# SCH_SecureGuardianDevice_2024-06-15.net
KiCad netlist of a schematic drawn in EasyEDA
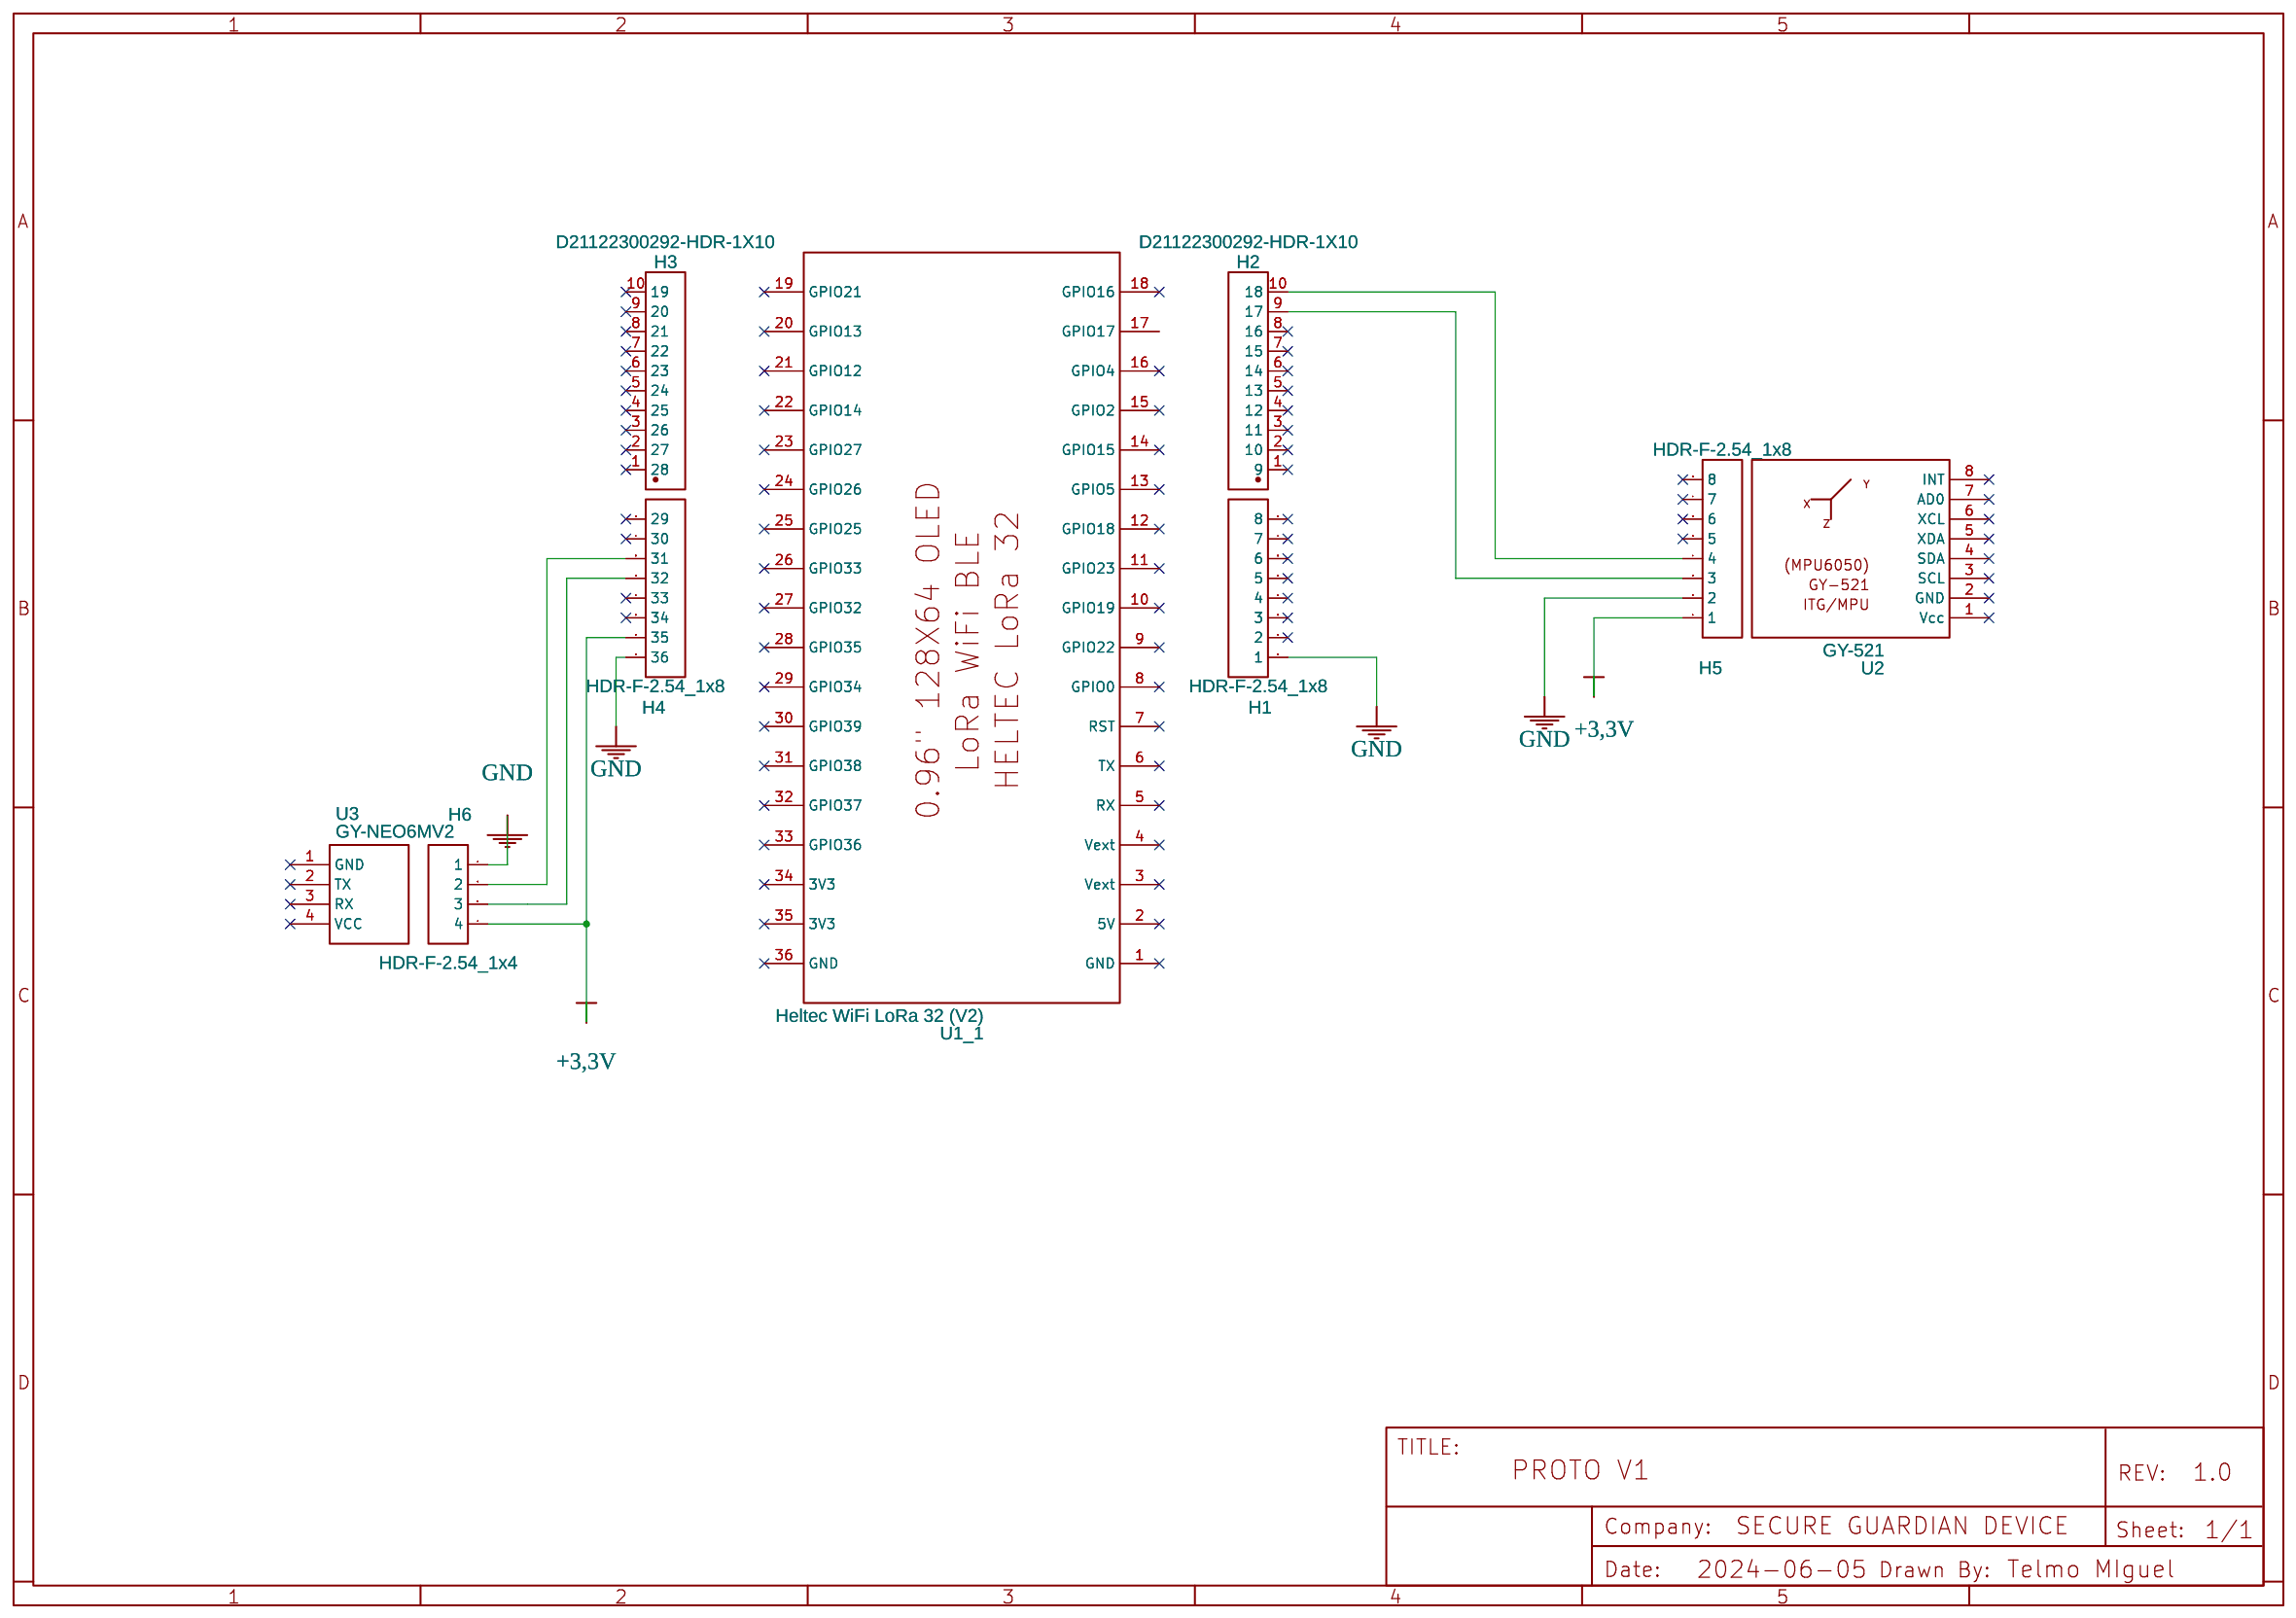
[diagram p0: schematic sheet]

(export (version "E")
  (design (tool "Eeschema 10.0.6"))
  (components
    (comp (ref "H1") (value "HDR-F-2.54_1x8") (libsource (lib "") (part "HDR-F-2.54_1x8")))
    (comp (ref "H2") (value "D21122300292-HDR-1X10") (libsource (lib "") (part "D21122300292-HDR-1X10")))
    (comp (ref "H3") (value "D21122300292-HDR-1X10") (libsource (lib "") (part "D21122300292-HDR-1X10_1")))
    (comp (ref "H4") (value "HDR-F-2.54_1x8") (libsource (lib "") (part "HDR-F-2.54_1x8_1")))
    (comp (ref "H5") (value "HDR-F-2.54_1x8") (libsource (lib "") (part "HDR-F-2.54_1x8_2")))
    (comp (ref "H6") (value "HDR-F-2.54_1x4") (libsource (lib "") (part "HDR-F-2.54_1x4")))
    (comp (ref "U1_1")
      (value "Heltec WiFi LoRa 32 (V2)")
      (fields
        (field (name "Manufacturer Part") "Heltec WiFi LoRa 32(V2)")
        (field (name "Manufacturer") "Heltec")
      )
      (libsource (lib "") (part "Heltec WiFi LoRa 32 (V2)"))
    )
    (comp (ref "U2") (value "GY-521") (libsource (lib "") (part "GY-521")))
    (comp (ref "U3") (value "GY-NEO6MV2") (libsource (lib "") (part "GY-NEO6MV2")))
  )
  (nets
    (net (code "1") (name "+3,3V") (class "Default")
      (node (ref "H4") (pin "2") (pinfunction "35_2") (pintype "unspecified"))
      (node (ref "H5") (pin "1") (pinfunction "1_1") (pintype "unspecified"))
      (node (ref "H6") (pin "4") (pinfunction "4_4") (pintype "unspecified"))
    )
    (net (code "2") (name "GND") (class "Default")
      (node (ref "H1") (pin "1") (pinfunction "1_1") (pintype "unspecified"))
      (node (ref "H4") (pin "1") (pinfunction "36_1") (pintype "unspecified"))
      (node (ref "H5") (pin "2") (pinfunction "2_2") (pintype "unspecified"))
      (node (ref "H6") (pin "1") (pinfunction "1_1") (pintype "unspecified"))
    )
    (net (code "3") (name "Net-(H2-17)") (class "Default")
      (node (ref "H2") (pin "9") (pinfunction "17_9") (pintype "unspecified"))
      (node (ref "H5") (pin "3") (pinfunction "3_3") (pintype "unspecified"))
    )
    (net (code "4") (name "Net-(H2-18)") (class "Default")
      (node (ref "H2") (pin "10") (pinfunction "18_10") (pintype "unspecified"))
      (node (ref "H5") (pin "4") (pinfunction "4_4") (pintype "unspecified"))
    )
    (net (code "5") (name "Net-(H4-31)") (class "Default")
      (node (ref "H4") (pin "6") (pinfunction "31_6") (pintype "unspecified"))
      (node (ref "H6") (pin "2") (pinfunction "2_2") (pintype "unspecified"))
    )
    (net (code "6") (name "Net-(H4-32)") (class "Default")
      (node (ref "H4") (pin "5") (pinfunction "32_5") (pintype "unspecified"))
      (node (ref "H6") (pin "3") (pinfunction "3_3") (pintype "unspecified"))
    )
    (net (code "7") (name "unconnected-(H1-Pad2)") (class "Default")
      (node (ref "H1") (pin "2") (pinfunction "2_2") (pintype "unspecified+no_connect"))
    )
    (net (code "8") (name "unconnected-(H1-Pad3)") (class "Default")
      (node (ref "H1") (pin "3") (pinfunction "3_3") (pintype "unspecified+no_connect"))
    )
    (net (code "9") (name "unconnected-(H1-Pad4)") (class "Default")
      (node (ref "H1") (pin "4") (pinfunction "4_4") (pintype "unspecified+no_connect"))
    )
    (net (code "10") (name "unconnected-(H1-Pad5)") (class "Default")
      (node (ref "H1") (pin "5") (pinfunction "5_5") (pintype "unspecified+no_connect"))
    )
    (net (code "11") (name "unconnected-(H1-Pad6)") (class "Default")
      (node (ref "H1") (pin "6") (pinfunction "6_6") (pintype "unspecified+no_connect"))
    )
    (net (code "12") (name "unconnected-(H1-Pad7)") (class "Default")
      (node (ref "H1") (pin "7") (pinfunction "7_7") (pintype "unspecified+no_connect"))
    )
    (net (code "13") (name "unconnected-(H1-Pad8)") (class "Default")
      (node (ref "H1") (pin "8") (pinfunction "8_8") (pintype "unspecified+no_connect"))
    )
    (net (code "14") (name "unconnected-(H2-9-Pad1)") (class "Default")
      (node (ref "H2") (pin "1") (pinfunction "9_1") (pintype "unspecified+no_connect"))
    )
    (net (code "15") (name "unconnected-(H2-10-Pad2)") (class "Default")
      (node (ref "H2") (pin "2") (pinfunction "10_2") (pintype "unspecified+no_connect"))
    )
    (net (code "16") (name "unconnected-(H2-11-Pad3)") (class "Default")
      (node (ref "H2") (pin "3") (pinfunction "11_3") (pintype "unspecified+no_connect"))
    )
    (net (code "17") (name "unconnected-(H2-12-Pad4)") (class "Default")
      (node (ref "H2") (pin "4") (pinfunction "12_4") (pintype "unspecified+no_connect"))
    )
    (net (code "18") (name "unconnected-(H2-13-Pad5)") (class "Default")
      (node (ref "H2") (pin "5") (pinfunction "13_5") (pintype "unspecified+no_connect"))
    )
    (net (code "19") (name "unconnected-(H2-14-Pad6)") (class "Default")
      (node (ref "H2") (pin "6") (pinfunction "14_6") (pintype "unspecified+no_connect"))
    )
    (net (code "20") (name "unconnected-(H2-15-Pad7)") (class "Default")
      (node (ref "H2") (pin "7") (pinfunction "15_7") (pintype "unspecified+no_connect"))
    )
    (net (code "21") (name "unconnected-(H2-16-Pad8)") (class "Default")
      (node (ref "H2") (pin "8") (pinfunction "16_8") (pintype "unspecified+no_connect"))
    )
    (net (code "22") (name "unconnected-(H3-19-Pad10)") (class "Default")
      (node (ref "H3") (pin "10") (pinfunction "19_10") (pintype "unspecified+no_connect"))
    )
    (net (code "23") (name "unconnected-(H3-20-Pad9)") (class "Default")
      (node (ref "H3") (pin "9") (pinfunction "20_9") (pintype "unspecified+no_connect"))
    )
    (net (code "24") (name "unconnected-(H3-21-Pad8)") (class "Default")
      (node (ref "H3") (pin "8") (pinfunction "21_8") (pintype "unspecified+no_connect"))
    )
    (net (code "25") (name "unconnected-(H3-22-Pad7)") (class "Default")
      (node (ref "H3") (pin "7") (pinfunction "22_7") (pintype "unspecified+no_connect"))
    )
    (net (code "26") (name "unconnected-(H3-23-Pad6)") (class "Default")
      (node (ref "H3") (pin "6") (pinfunction "23_6") (pintype "unspecified+no_connect"))
    )
    (net (code "27") (name "unconnected-(H3-24-Pad5)") (class "Default")
      (node (ref "H3") (pin "5") (pinfunction "24_5") (pintype "unspecified+no_connect"))
    )
    (net (code "28") (name "unconnected-(H3-25-Pad4)") (class "Default")
      (node (ref "H3") (pin "4") (pinfunction "25_4") (pintype "unspecified+no_connect"))
    )
    (net (code "29") (name "unconnected-(H3-26-Pad3)") (class "Default")
      (node (ref "H3") (pin "3") (pinfunction "26_3") (pintype "unspecified+no_connect"))
    )
    (net (code "30") (name "unconnected-(H3-27-Pad2)") (class "Default")
      (node (ref "H3") (pin "2") (pinfunction "27_2") (pintype "unspecified+no_connect"))
    )
    (net (code "31") (name "unconnected-(H3-28-Pad1)") (class "Default")
      (node (ref "H3") (pin "1") (pinfunction "28_1") (pintype "unspecified+no_connect"))
    )
    (net (code "32") (name "unconnected-(H4-29-Pad8)") (class "Default")
      (node (ref "H4") (pin "8") (pinfunction "29_8") (pintype "unspecified+no_connect"))
    )
    (net (code "33") (name "unconnected-(H4-30-Pad7)") (class "Default")
      (node (ref "H4") (pin "7") (pinfunction "30_7") (pintype "unspecified+no_connect"))
    )
    (net (code "34") (name "unconnected-(H4-33-Pad4)") (class "Default")
      (node (ref "H4") (pin "4") (pinfunction "33_4") (pintype "unspecified+no_connect"))
    )
    (net (code "35") (name "unconnected-(H4-34-Pad3)") (class "Default")
      (node (ref "H4") (pin "3") (pinfunction "34_3") (pintype "unspecified+no_connect"))
    )
    (net (code "36") (name "unconnected-(H5-Pad5)") (class "Default")
      (node (ref "H5") (pin "5") (pinfunction "5_5") (pintype "unspecified+no_connect"))
    )
    (net (code "37") (name "unconnected-(H5-Pad6)") (class "Default")
      (node (ref "H5") (pin "6") (pinfunction "6_6") (pintype "unspecified+no_connect"))
    )
    (net (code "38") (name "unconnected-(H5-Pad7)") (class "Default")
      (node (ref "H5") (pin "7") (pinfunction "7_7") (pintype "unspecified+no_connect"))
    )
    (net (code "39") (name "unconnected-(H5-Pad8)") (class "Default")
      (node (ref "H5") (pin "8") (pinfunction "8_8") (pintype "unspecified+no_connect"))
    )
    (net (code "40") (name "unconnected-(U1_1-3V3-Pad34)") (class "Default")
      (node (ref "U1_1") (pin "34") (pinfunction "3V3_34") (pintype "unspecified+no_connect"))
    )
    (net (code "41") (name "unconnected-(U1_1-3V3-Pad35)") (class "Default")
      (node (ref "U1_1") (pin "35") (pinfunction "3V3_35") (pintype "unspecified+no_connect"))
    )
    (net (code "42") (name "unconnected-(U1_1-5V-Pad2)") (class "Default")
      (node (ref "U1_1") (pin "2") (pinfunction "5V_2") (pintype "unspecified+no_connect"))
    )
    (net (code "43") (name "unconnected-(U1_1-GND-Pad1)") (class "Default")
      (node (ref "U1_1") (pin "1") (pinfunction "GND_1") (pintype "unspecified+no_connect"))
    )
    (net (code "44") (name "unconnected-(U1_1-GND-Pad36)") (class "Default")
      (node (ref "U1_1") (pin "36") (pinfunction "GND_36") (pintype "unspecified+no_connect"))
    )
    (net (code "45") (name "unconnected-(U1_1-GPIO0-Pad8)") (class "Default")
      (node (ref "U1_1") (pin "8") (pinfunction "GPIO0_8") (pintype "unspecified+no_connect"))
    )
    (net (code "46") (name "unconnected-(U1_1-GPIO2-Pad15)") (class "Default")
      (node (ref "U1_1") (pin "15") (pinfunction "GPIO2_15") (pintype "unspecified+no_connect"))
    )
    (net (code "47") (name "unconnected-(U1_1-GPIO4-Pad16)") (class "Default")
      (node (ref "U1_1") (pin "16") (pinfunction "GPIO4_16") (pintype "unspecified+no_connect"))
    )
    (net (code "48") (name "unconnected-(U1_1-GPIO5-Pad13)") (class "Default")
      (node (ref "U1_1") (pin "13") (pinfunction "GPIO5_13") (pintype "unspecified+no_connect"))
    )
    (net (code "49") (name "unconnected-(U1_1-GPIO12-Pad21)") (class "Default")
      (node (ref "U1_1") (pin "21") (pinfunction "GPIO12_21") (pintype "unspecified+no_connect"))
    )
    (net (code "50") (name "unconnected-(U1_1-GPIO13-Pad20)") (class "Default")
      (node (ref "U1_1") (pin "20") (pinfunction "GPIO13_20") (pintype "unspecified+no_connect"))
    )
    (net (code "51") (name "unconnected-(U1_1-GPIO14-Pad22)") (class "Default")
      (node (ref "U1_1") (pin "22") (pinfunction "GPIO14_22") (pintype "unspecified+no_connect"))
    )
    (net (code "52") (name "unconnected-(U1_1-GPIO15-Pad14)") (class "Default")
      (node (ref "U1_1") (pin "14") (pinfunction "GPIO15_14") (pintype "unspecified+no_connect"))
    )
    (net (code "53") (name "unconnected-(U1_1-GPIO16-Pad18)") (class "Default")
      (node (ref "U1_1") (pin "18") (pinfunction "GPIO16_18") (pintype "unspecified+no_connect"))
    )
    (net (code "54") (name "unconnected-(U1_1-GPIO17-Pad17)") (class "Default")
      (node (ref "U1_1") (pin "17") (pinfunction "GPIO17_17") (pintype "unspecified"))
    )
    (net (code "55") (name "unconnected-(U1_1-GPIO18-Pad12)") (class "Default")
      (node (ref "U1_1") (pin "12") (pinfunction "GPIO18_12") (pintype "unspecified+no_connect"))
    )
    (net (code "56") (name "unconnected-(U1_1-GPIO19-Pad10)") (class "Default")
      (node (ref "U1_1") (pin "10") (pinfunction "GPIO19_10") (pintype "unspecified+no_connect"))
    )
    (net (code "57") (name "unconnected-(U1_1-GPIO21-Pad19)") (class "Default")
      (node (ref "U1_1") (pin "19") (pinfunction "GPIO21_19") (pintype "unspecified+no_connect"))
    )
    (net (code "58") (name "unconnected-(U1_1-GPIO22-Pad9)") (class "Default")
      (node (ref "U1_1") (pin "9") (pinfunction "GPIO22_9") (pintype "unspecified+no_connect"))
    )
    (net (code "59") (name "unconnected-(U1_1-GPIO23-Pad11)") (class "Default")
      (node (ref "U1_1") (pin "11") (pinfunction "GPIO23_11") (pintype "unspecified+no_connect"))
    )
    (net (code "60") (name "unconnected-(U1_1-GPIO25-Pad25)") (class "Default")
      (node (ref "U1_1") (pin "25") (pinfunction "GPIO25_25") (pintype "unspecified+no_connect"))
    )
    (net (code "61") (name "unconnected-(U1_1-GPIO26-Pad24)") (class "Default")
      (node (ref "U1_1") (pin "24") (pinfunction "GPIO26_24") (pintype "unspecified+no_connect"))
    )
    (net (code "62") (name "unconnected-(U1_1-GPIO27-Pad23)") (class "Default")
      (node (ref "U1_1") (pin "23") (pinfunction "GPIO27_23") (pintype "unspecified+no_connect"))
    )
    (net (code "63") (name "unconnected-(U1_1-GPIO32-Pad27)") (class "Default")
      (node (ref "U1_1") (pin "27") (pinfunction "GPIO32_27") (pintype "unspecified+no_connect"))
    )
    (net (code "64") (name "unconnected-(U1_1-GPIO33-Pad26)") (class "Default")
      (node (ref "U1_1") (pin "26") (pinfunction "GPIO33_26") (pintype "unspecified+no_connect"))
    )
    (net (code "65") (name "unconnected-(U1_1-GPIO34-Pad29)") (class "Default")
      (node (ref "U1_1") (pin "29") (pinfunction "GPIO34_29") (pintype "unspecified+no_connect"))
    )
    (net (code "66") (name "unconnected-(U1_1-GPIO35-Pad28)") (class "Default")
      (node (ref "U1_1") (pin "28") (pinfunction "GPIO35_28") (pintype "unspecified+no_connect"))
    )
    (net (code "67") (name "unconnected-(U1_1-GPIO36-Pad33)") (class "Default")
      (node (ref "U1_1") (pin "33") (pinfunction "GPIO36_33") (pintype "unspecified+no_connect"))
    )
    (net (code "68") (name "unconnected-(U1_1-GPIO37-Pad32)") (class "Default")
      (node (ref "U1_1") (pin "32") (pinfunction "GPIO37_32") (pintype "unspecified+no_connect"))
    )
    (net (code "69") (name "unconnected-(U1_1-GPIO38-Pad31)") (class "Default")
      (node (ref "U1_1") (pin "31") (pinfunction "GPIO38_31") (pintype "unspecified+no_connect"))
    )
    (net (code "70") (name "unconnected-(U1_1-GPIO39-Pad30)") (class "Default")
      (node (ref "U1_1") (pin "30") (pinfunction "GPIO39_30") (pintype "unspecified+no_connect"))
    )
    (net (code "71") (name "unconnected-(U1_1-RST-Pad7)") (class "Default")
      (node (ref "U1_1") (pin "7") (pinfunction "RST_7") (pintype "unspecified+no_connect"))
    )
    (net (code "72") (name "unconnected-(U1_1-RX-Pad5)") (class "Default")
      (node (ref "U1_1") (pin "5") (pinfunction "RX_5") (pintype "unspecified+no_connect"))
    )
    (net (code "73") (name "unconnected-(U1_1-TX-Pad6)") (class "Default")
      (node (ref "U1_1") (pin "6") (pinfunction "TX_6") (pintype "unspecified+no_connect"))
    )
    (net (code "74") (name "unconnected-(U1_1-Vext-Pad3)") (class "Default")
      (node (ref "U1_1") (pin "3") (pinfunction "Vext_3") (pintype "unspecified+no_connect"))
    )
    (net (code "75") (name "unconnected-(U1_1-Vext-Pad4)") (class "Default")
      (node (ref "U1_1") (pin "4") (pinfunction "Vext_4") (pintype "unspecified+no_connect"))
    )
    (net (code "76") (name "unconnected-(U2-AD0-Pad7)") (class "Default")
      (node (ref "U2") (pin "7") (pinfunction "AD0_7") (pintype "unspecified+no_connect"))
    )
    (net (code "77") (name "unconnected-(U2-GND-Pad2)") (class "Default")
      (node (ref "U2") (pin "2") (pinfunction "GND_2") (pintype "unspecified+no_connect"))
    )
    (net (code "78") (name "unconnected-(U2-INT-Pad8)") (class "Default")
      (node (ref "U2") (pin "8") (pinfunction "INT_8") (pintype "unspecified+no_connect"))
    )
    (net (code "79") (name "unconnected-(U2-SCL-Pad3)") (class "Default")
      (node (ref "U2") (pin "3") (pinfunction "SCL_3") (pintype "unspecified+no_connect"))
    )
    (net (code "80") (name "unconnected-(U2-SDA-Pad4)") (class "Default")
      (node (ref "U2") (pin "4") (pinfunction "SDA_4") (pintype "unspecified+no_connect"))
    )
    (net (code "81") (name "unconnected-(U2-Vcc-Pad1)") (class "Default")
      (node (ref "U2") (pin "1") (pinfunction "Vcc_1") (pintype "unspecified+no_connect"))
    )
    (net (code "82") (name "unconnected-(U2-XCL-Pad6)") (class "Default")
      (node (ref "U2") (pin "6") (pinfunction "XCL_6") (pintype "unspecified+no_connect"))
    )
    (net (code "83") (name "unconnected-(U2-XDA-Pad5)") (class "Default")
      (node (ref "U2") (pin "5") (pinfunction "XDA_5") (pintype "unspecified+no_connect"))
    )
    (net (code "84") (name "unconnected-(U3-GND-Pad1)") (class "Default")
      (node (ref "U3") (pin "1") (pinfunction "GND_1") (pintype "unspecified+no_connect"))
    )
    (net (code "85") (name "unconnected-(U3-RX-Pad3)") (class "Default")
      (node (ref "U3") (pin "3") (pinfunction "RX_3") (pintype "unspecified+no_connect"))
    )
    (net (code "86") (name "unconnected-(U3-TX-Pad2)") (class "Default")
      (node (ref "U3") (pin "2") (pinfunction "TX_2") (pintype "unspecified+no_connect"))
    )
    (net (code "87") (name "unconnected-(U3-VCC-Pad4)") (class "Default")
      (node (ref "U3") (pin "4") (pinfunction "VCC_4") (pintype "unspecified+no_connect"))
    )
  )
)
